# sensor_battery.net
KiCad netlist of a schematic drawn in EAGLE
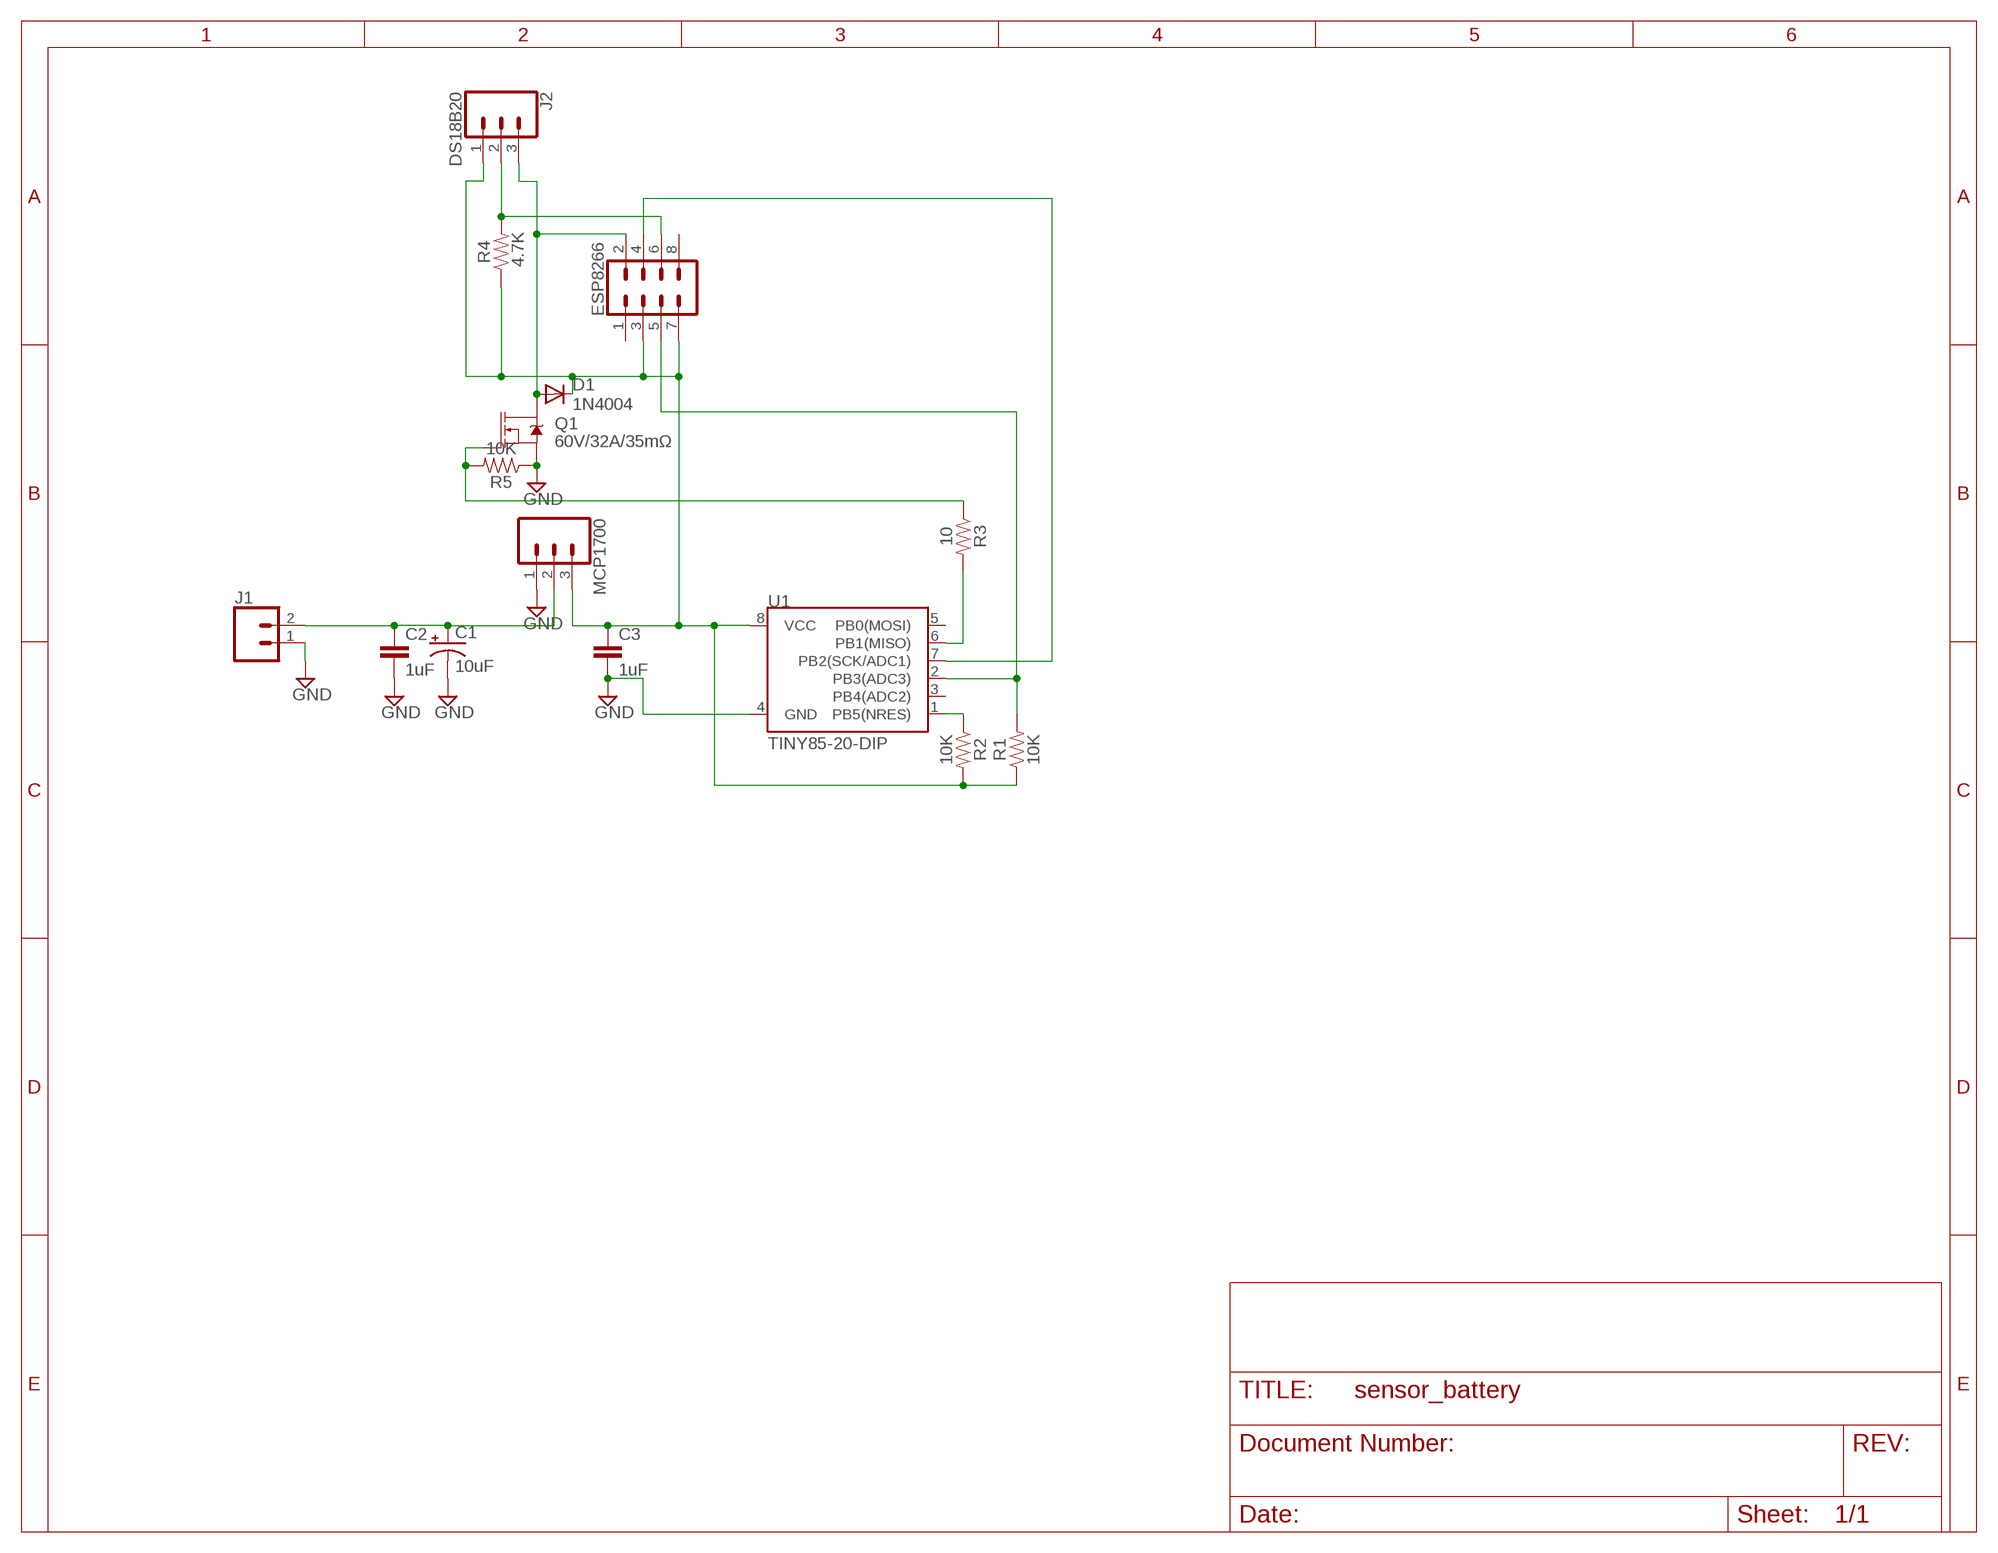
[diagram p0: schematic, sheet 1]

(export (version "E")
  (design (tool "Eeschema 10.0.6"))
  (components
    (comp (ref "C1")
      (value "10uF")
      (footprint "eagle-import:CPOL-RADIAL-2.5MM-5MM")
      (libsource (lib "eagle-import") (part "10UF-POLAR-RADIAL-2.5MM-25V-20%"))
    )
    (comp (ref "C2")
      (value "1uF")
      (footprint "eagle-import:C5B2.5")
      (libsource (lib "eagle-import") (part "C5/2.5"))
    )
    (comp (ref "C3")
      (value "1uF")
      (footprint "eagle-import:C5B2.5")
      (libsource (lib "eagle-import") (part "C5/2.5"))
    )
    (comp (ref "D1")
      (value "1N4004")
      (footprint "eagle-import:DO41-10")
      (libsource (lib "eagle-import") (part "1N4004"))
    )
    (comp (ref "ESP8266")
      (value "CONN_04X2")
      (footprint "eagle-import:2X4")
      (libsource (lib "eagle-import") (part "CONN_04X2"))
    )
    (comp (ref "J1")
      (value "CONN_02-JST-2-PTH-NO_SILK")
      (footprint "eagle-import:JST-2-PTH-NS")
      (libsource (lib "eagle-import") (part "CONN_02-JST-2-PTH-NO_SILK"))
    )
    (comp (ref "J2")
      (value "DS18B20")
      (footprint "eagle-import:JST-3-PTH")
      (libsource (lib "eagle-import") (part "CONN_03JST-PTH"))
    )
    (comp (ref "MCP1700")
      (value "CONN_03")
      (footprint "eagle-import:1X03")
      (libsource (lib "eagle-import") (part "CONN_03"))
    )
    (comp (ref "Q1")
      (value "60V/32A/35mΩ")
      (footprint "eagle-import:TO220V")
      (libsource (lib "eagle-import") (part "MOSFET-NCH-FQP30N06L"))
    )
    (comp (ref "R1")
      (value "10K")
      (footprint "eagle-import:AXIAL-0.3")
      (libsource (lib "eagle-import") (part "10OHM-HORIZ-1/4W-1%"))
    )
    (comp (ref "R2")
      (value "10K")
      (footprint "eagle-import:AXIAL-0.3")
      (libsource (lib "eagle-import") (part "10OHM-HORIZ-1/4W-1%"))
    )
    (comp (ref "R3")
      (value "10")
      (footprint "eagle-import:AXIAL-0.3")
      (libsource (lib "eagle-import") (part "10OHM-HORIZ-1/4W-1%"))
    )
    (comp (ref "R4")
      (value "4.7K")
      (footprint "eagle-import:AXIAL-0.3")
      (libsource (lib "eagle-import") (part "RESISTORAXIAL-0.3"))
    )
    (comp (ref "R5")
      (value "10K")
      (footprint "eagle-import:AXIAL-0.3")
      (libsource (lib "eagle-import") (part "10OHM-HORIZ-1/4W-1%"))
    )
    (comp (ref "U1")
      (value "TINY85-20-DIP")
      (footprint "eagle-import:DIP08_MCU")
      (libsource (lib "eagle-import") (part "ATTINY45TINY85-20-DIP"))
    )
  )
  (nets
    (net (code "1") (name "GND") (class "Default")
      (node (ref "C1") (pin "2") (pinfunction "-_2") (pintype "passive"))
      (node (ref "C2") (pin "2") (pinfunction "2_2") (pintype "passive"))
      (node (ref "C3") (pin "2") (pinfunction "2_2") (pintype "passive"))
      (node (ref "J1") (pin "1") (pinfunction "1_1") (pintype "passive"))
      (node (ref "MCP1700") (pin "1") (pinfunction "1_1") (pintype "passive"))
      (node (ref "Q1") (pin "3") (pinfunction "S_3") (pintype "bidirectional"))
      (node (ref "R5") (pin "P$1") (pinfunction "1_P$1") (pintype "passive"))
      (node (ref "U1") (pin "4") (pinfunction "GND_4") (pintype "bidirectional"))
    )
    (net (code "2") (name "Net-(C1-+)") (class "Default")
      (node (ref "C1") (pin "1") (pinfunction "+_1") (pintype "passive"))
      (node (ref "C2") (pin "1") (pinfunction "1_1") (pintype "passive"))
      (node (ref "J1") (pin "2") (pinfunction "2_2") (pintype "passive"))
      (node (ref "MCP1700") (pin "2") (pinfunction "2_2") (pintype "passive"))
    )
    (net (code "3") (name "Net-(Q1-D)") (class "Default")
      (node (ref "D1") (pin "A") (pinfunction "A_A") (pintype "passive"))
      (node (ref "ESP8266") (pin "2") (pinfunction "2_2") (pintype "passive"))
      (node (ref "J2") (pin "3") (pinfunction "3_3") (pintype "passive"))
      (node (ref "Q1") (pin "2") (pinfunction "D_2") (pintype "bidirectional"))
    )
    (net (code "4") (name "Net-(Q1-G)") (class "Default")
      (node (ref "Q1") (pin "1") (pinfunction "G_1") (pintype "bidirectional"))
      (node (ref "R3") (pin "P$1") (pinfunction "1_P$1") (pintype "passive"))
      (node (ref "R5") (pin "P$2") (pinfunction "2_P$2") (pintype "passive"))
    )
    (net (code "5") (name "Net-(R1-1)") (class "Default")
      (node (ref "C3") (pin "1") (pinfunction "1_1") (pintype "passive"))
      (node (ref "D1") (pin "C") (pinfunction "C_C") (pintype "passive"))
      (node (ref "ESP8266") (pin "3") (pinfunction "3_3") (pintype "passive"))
      (node (ref "ESP8266") (pin "7") (pinfunction "7_7") (pintype "passive"))
      (node (ref "J2") (pin "1") (pinfunction "1_1") (pintype "passive"))
      (node (ref "MCP1700") (pin "3") (pinfunction "3_3") (pintype "passive"))
      (node (ref "R1") (pin "P$1") (pinfunction "1_P$1") (pintype "passive"))
      (node (ref "R2") (pin "P$2") (pinfunction "2_P$2") (pintype "passive"))
      (node (ref "R4") (pin "P$1") (pinfunction "1_P$1") (pintype "passive"))
      (node (ref "U1") (pin "8") (pinfunction "VCC_8") (pintype "bidirectional"))
    )
    (net (code "6") (name "Net-(R1-2)") (class "Default")
      (node (ref "ESP8266") (pin "5") (pinfunction "5_5") (pintype "passive"))
      (node (ref "R1") (pin "P$2") (pinfunction "2_P$2") (pintype "passive"))
      (node (ref "U1") (pin "2") (pinfunction "PB3(ADC3)_2") (pintype "bidirectional"))
    )
    (net (code "7") (name "Net-(R2-1)") (class "Default")
      (node (ref "R2") (pin "P$1") (pinfunction "1_P$1") (pintype "passive"))
      (node (ref "U1") (pin "1") (pinfunction "PB5(NRES)_1") (pintype "bidirectional"))
    )
    (net (code "8") (name "Net-(R3-2)") (class "Default")
      (node (ref "R3") (pin "P$2") (pinfunction "2_P$2") (pintype "passive"))
      (node (ref "U1") (pin "6") (pinfunction "PB1(MISO)_6") (pintype "bidirectional"))
    )
    (net (code "9") (name "Net-(R4-2)") (class "Default")
      (node (ref "ESP8266") (pin "6") (pinfunction "6_6") (pintype "passive"))
      (node (ref "J2") (pin "2") (pinfunction "2_2") (pintype "passive"))
      (node (ref "R4") (pin "P$2") (pinfunction "2_P$2") (pintype "passive"))
    )
    (net (code "10") (name "Net-(U1-PB2(SCK{slash}ADC1))") (class "Default")
      (node (ref "ESP8266") (pin "4") (pinfunction "4_4") (pintype "passive"))
      (node (ref "U1") (pin "7") (pinfunction "PB2(SCK/ADC1)_7") (pintype "bidirectional"))
    )
    (net (code "11") (name "unconnected-(ESP8266-Pad1)") (class "Default")
      (node (ref "ESP8266") (pin "1") (pinfunction "1_1") (pintype "passive"))
    )
    (net (code "12") (name "unconnected-(ESP8266-Pad8)") (class "Default")
      (node (ref "ESP8266") (pin "8") (pinfunction "8_8") (pintype "passive"))
    )
    (net (code "13") (name "unconnected-(U1-PB0(MOSI)-Pad5)") (class "Default")
      (node (ref "U1") (pin "5") (pinfunction "PB0(MOSI)_5") (pintype "bidirectional"))
    )
    (net (code "14") (name "unconnected-(U1-PB4(ADC2)-Pad3)") (class "Default")
      (node (ref "U1") (pin "3") (pinfunction "PB4(ADC2)_3") (pintype "bidirectional"))
    )
  )
)
